# remote_emergency_switch.net
KiCad netlist of a schematic drawn in EAGLE
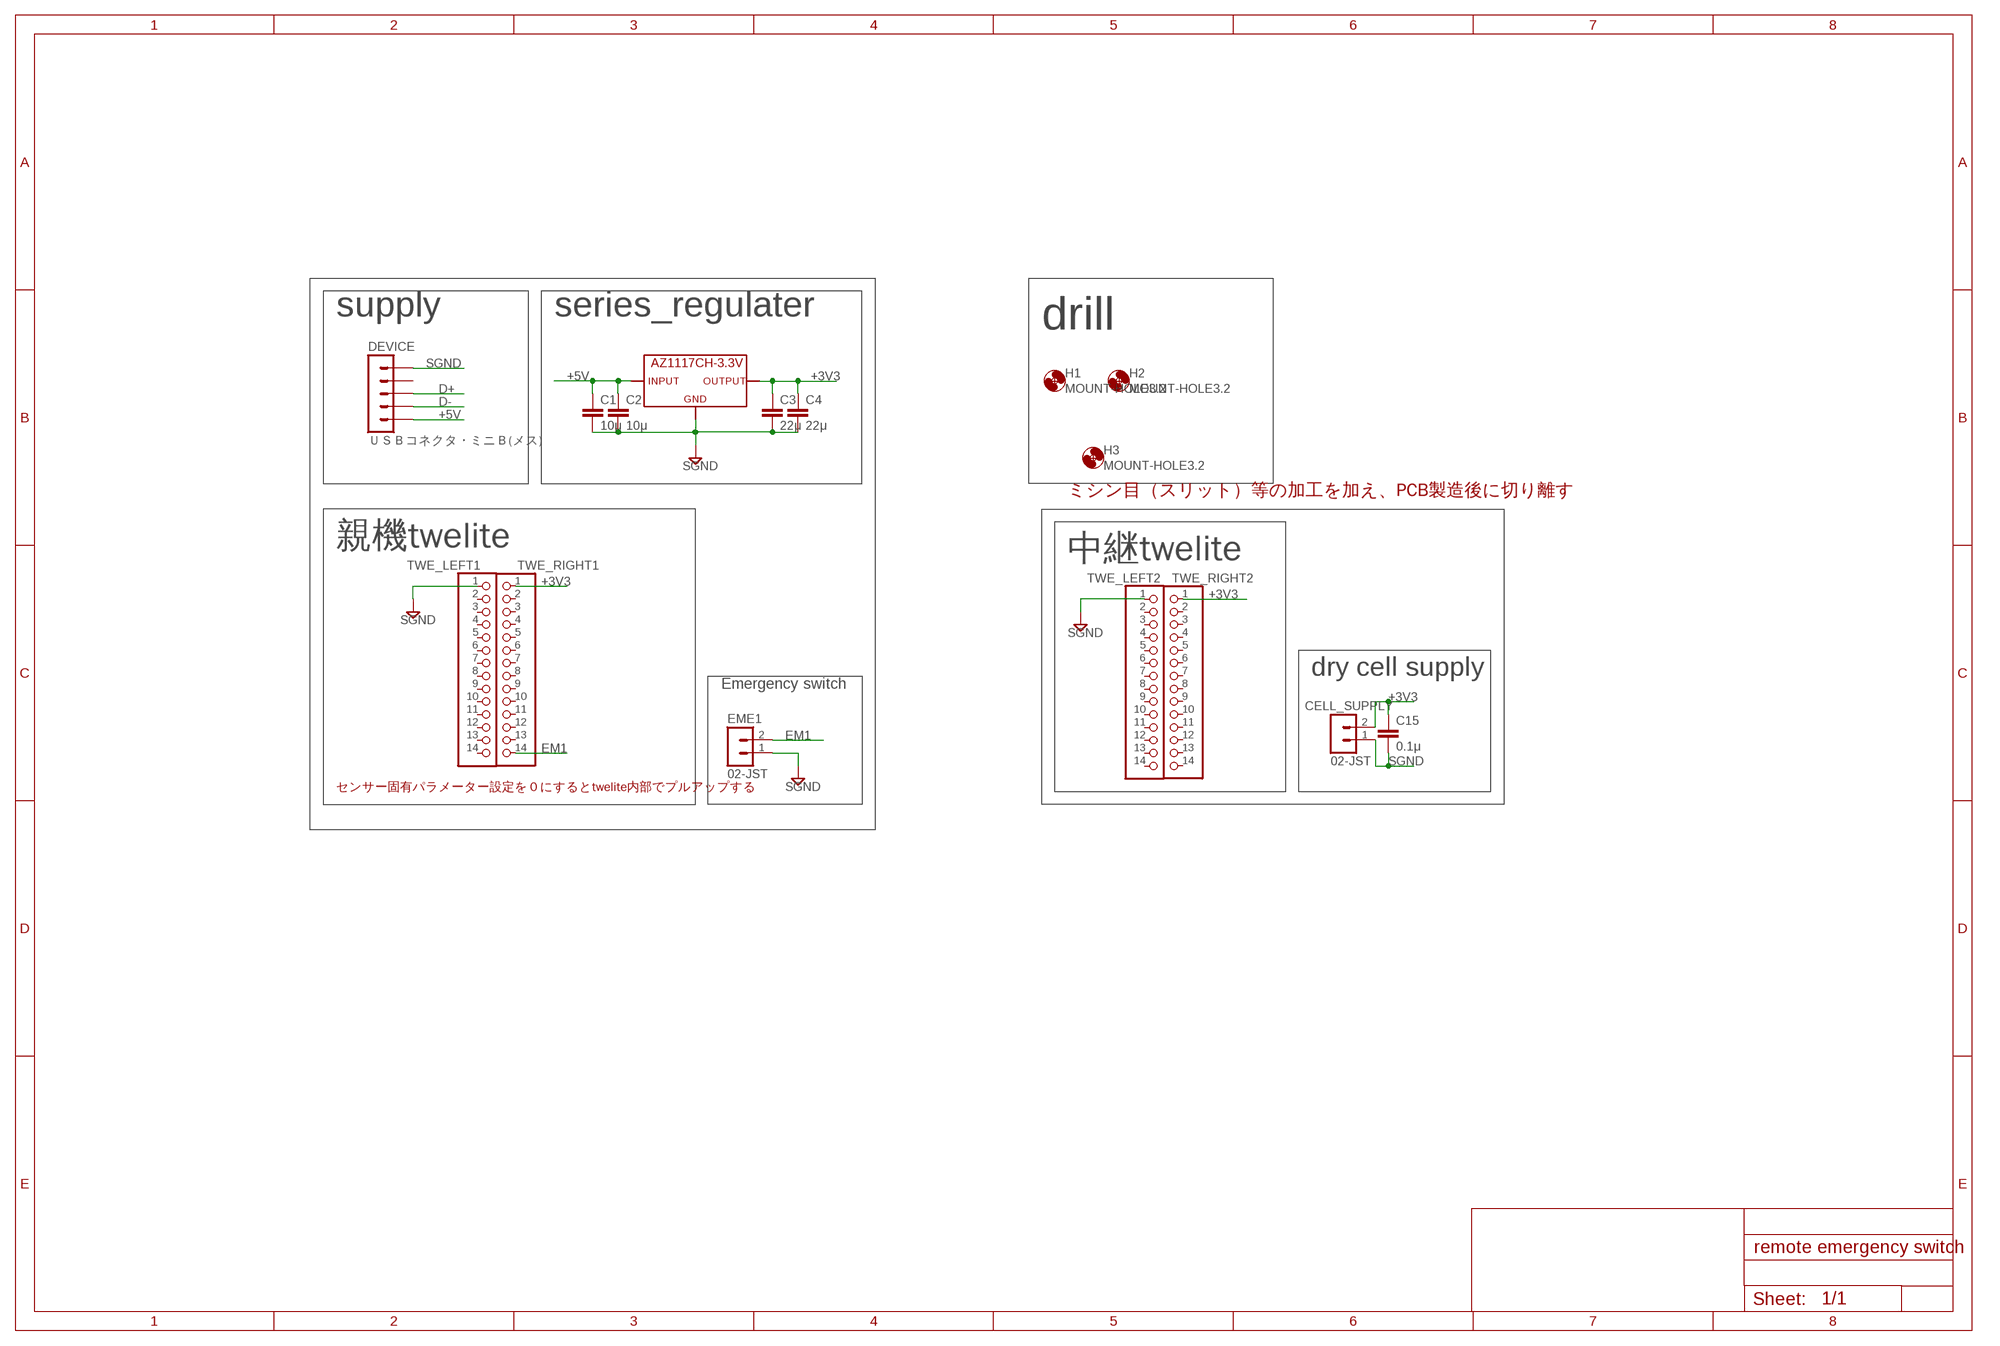
[diagram p0: schematic, sheet 1]

(export (version "E")
  (design (tool "Eeschema 10.0.6"))
  (components
    (comp (ref "C1")
      (value "10μ")
      (footprint "eagle-import:GRM0335C1E240GA01D")
      (libsource (lib "eagle-import") (part "GRM0335C1E240GA01D"))
    )
    (comp (ref "C2")
      (value "10μ")
      (footprint "eagle-import:GRM0335C1E240GA01D")
      (libsource (lib "eagle-import") (part "GRM0335C1E240GA01D"))
    )
    (comp (ref "C3")
      (value "22μ")
      (footprint "eagle-import:GRM0335C1E240GA01D")
      (libsource (lib "eagle-import") (part "GRM0335C1E240GA01D"))
    )
    (comp (ref "C4")
      (value "22μ")
      (footprint "eagle-import:GRM0335C1E240GA01D")
      (libsource (lib "eagle-import") (part "GRM0335C1E240GA01D"))
    )
    (comp (ref "C15")
      (value "0.1μ")
      (footprint "eagle-import:C025-024X044")
      (libsource (lib "eagle-import") (part "C-EU025-024X044"))
    )
    (comp (ref "CELL_SUPPLY")
      (value "02-JST")
      (footprint "eagle-import:B2B-XH")
      (libsource (lib "eagle-import") (part "02-JST"))
    )
    (comp (ref "DEVICE")
      (value "ＵＳＢコネクタ・ミニＢ(メス)")
      (footprint "eagle-import:ＵＳＢコネクタ・ミニＢ(メス)")
      (libsource (lib "eagle-import") (part "ＵＳＢコネクタ・ミニＢ(メス)"))
    )
    (comp (ref "EME1")
      (value "02-JST")
      (footprint "eagle-import:B2B-XH")
      (libsource (lib "eagle-import") (part "02-JST"))
    )
    (comp (ref "H1")
      (value "MOUNT-HOLE3.2")
      (footprint "eagle-import:3,2")
      (libsource (lib "eagle-import") (part "MOUNT-HOLE3.2"))
    )
    (comp (ref "H2")
      (value "MOUNT-HOLE3.2")
      (footprint "eagle-import:3,2")
      (libsource (lib "eagle-import") (part "MOUNT-HOLE3.2"))
    )
    (comp (ref "H3")
      (value "MOUNT-HOLE3.2")
      (footprint "eagle-import:3,2")
      (libsource (lib "eagle-import") (part "MOUNT-HOLE3.2"))
    )
    (comp (ref "REGYURETA")
      (value "３．３V")
      (footprint "eagle-import:ＡＺ１１１７ＣＨ－３．３ＴＲＧ１")
      (libsource (lib "eagle-import") (part "ＡＺ１１１７ＣＨ－３．３ＴＲＧ１"))
    )
    (comp (ref "TWE_LEFT1")
      (value "PINHD-1X14")
      (footprint "eagle-import:1X14")
      (libsource (lib "eagle-import") (part "PINHD-1X14"))
    )
    (comp (ref "TWE_LEFT2")
      (value "PINHD-1X14")
      (footprint "eagle-import:1X14")
      (libsource (lib "eagle-import") (part "PINHD-1X14"))
    )
    (comp (ref "TWE_RIGHT1")
      (value "PINHD-1X14")
      (footprint "eagle-import:1X14")
      (libsource (lib "eagle-import") (part "PINHD-1X14"))
    )
    (comp (ref "TWE_RIGHT2")
      (value "PINHD-1X14")
      (footprint "eagle-import:1X14")
      (libsource (lib "eagle-import") (part "PINHD-1X14"))
    )
  )
  (nets
    (net (code "1") (name "/+3V3") (class "Default")
      (node (ref "C15") (pin "1") (pinfunction "1_1") (pintype "passive"))
      (node (ref "C3") (pin "1") (pinfunction "1_1") (pintype "passive"))
      (node (ref "C4") (pin "1") (pinfunction "1_1") (pintype "passive"))
      (node (ref "CELL_SUPPLY") (pin "2") (pinfunction "2_2") (pintype "passive"))
      (node (ref "REGYURETA") (pin "OUTPUT") (pinfunction "OUTPUT_OUTPUT") (pintype "bidirectional"))
      (node (ref "REGYURETA") (pin "VOUT") (pinfunction "OUTPUT_VOUT") (pintype "bidirectional"))
      (node (ref "TWE_RIGHT1") (pin "1") (pinfunction "1_1") (pintype "passive"))
      (node (ref "TWE_RIGHT2") (pin "1") (pinfunction "1_1") (pintype "passive"))
    )
    (net (code "2") (name "/+5V") (class "Default")
      (node (ref "C1") (pin "1") (pinfunction "1_1") (pintype "passive"))
      (node (ref "C2") (pin "1") (pinfunction "1_1") (pintype "passive"))
      (node (ref "DEVICE") (pin "VBUS") (pinfunction "1_VBUS") (pintype "passive"))
      (node (ref "REGYURETA") (pin "INPUT") (pinfunction "INPUT_INPUT") (pintype "bidirectional"))
    )
    (net (code "3") (name "/D+") (class "Default")
      (node (ref "DEVICE") (pin "D+") (pinfunction "3_D+") (pintype "passive"))
    )
    (net (code "4") (name "/D-") (class "Default")
      (node (ref "DEVICE") (pin "D-") (pinfunction "2_D-") (pintype "passive"))
    )
    (net (code "5") (name "/EM1") (class "Default")
      (node (ref "EME1") (pin "2") (pinfunction "2_2") (pintype "passive"))
      (node (ref "TWE_RIGHT1") (pin "14") (pinfunction "14_14") (pintype "passive"))
    )
    (net (code "6") (name "GND") (class "Default")
      (node (ref "C1") (pin "2") (pinfunction "2_2") (pintype "passive"))
      (node (ref "C15") (pin "2") (pinfunction "2_2") (pintype "passive"))
      (node (ref "C2") (pin "2") (pinfunction "2_2") (pintype "passive"))
      (node (ref "C3") (pin "2") (pinfunction "2_2") (pintype "passive"))
      (node (ref "C4") (pin "2") (pinfunction "2_2") (pintype "passive"))
      (node (ref "CELL_SUPPLY") (pin "1") (pinfunction "1_1") (pintype "passive"))
      (node (ref "DEVICE") (pin "GND") (pinfunction "5_GND") (pintype "passive"))
      (node (ref "EME1") (pin "1") (pinfunction "1_1") (pintype "passive"))
      (node (ref "REGYURETA") (pin "ADJ/GND") (pinfunction "GND_ADJ/GND") (pintype "bidirectional"))
      (node (ref "TWE_LEFT1") (pin "1") (pinfunction "1_1") (pintype "passive"))
      (node (ref "TWE_LEFT2") (pin "1") (pinfunction "1_1") (pintype "passive"))
    )
    (net (code "7") (name "unconnected-(DEVICE-4-PadID)") (class "Default")
      (node (ref "DEVICE") (pin "ID") (pinfunction "4_ID") (pintype "passive"))
    )
    (net (code "8") (name "unconnected-(TWE_LEFT1-Pad2)") (class "Default")
      (node (ref "TWE_LEFT1") (pin "2") (pinfunction "2_2") (pintype "passive"))
    )
    (net (code "9") (name "unconnected-(TWE_LEFT1-Pad3)") (class "Default")
      (node (ref "TWE_LEFT1") (pin "3") (pinfunction "3_3") (pintype "passive"))
    )
    (net (code "10") (name "unconnected-(TWE_LEFT1-Pad4)") (class "Default")
      (node (ref "TWE_LEFT1") (pin "4") (pinfunction "4_4") (pintype "passive"))
    )
    (net (code "11") (name "unconnected-(TWE_LEFT1-Pad5)") (class "Default")
      (node (ref "TWE_LEFT1") (pin "5") (pinfunction "5_5") (pintype "passive"))
    )
    (net (code "12") (name "unconnected-(TWE_LEFT1-Pad6)") (class "Default")
      (node (ref "TWE_LEFT1") (pin "6") (pinfunction "6_6") (pintype "passive"))
    )
    (net (code "13") (name "unconnected-(TWE_LEFT1-Pad7)") (class "Default")
      (node (ref "TWE_LEFT1") (pin "7") (pinfunction "7_7") (pintype "passive"))
    )
    (net (code "14") (name "unconnected-(TWE_LEFT1-Pad8)") (class "Default")
      (node (ref "TWE_LEFT1") (pin "8") (pinfunction "8_8") (pintype "passive"))
    )
    (net (code "15") (name "unconnected-(TWE_LEFT1-Pad9)") (class "Default")
      (node (ref "TWE_LEFT1") (pin "9") (pinfunction "9_9") (pintype "passive"))
    )
    (net (code "16") (name "unconnected-(TWE_LEFT1-Pad10)") (class "Default")
      (node (ref "TWE_LEFT1") (pin "10") (pinfunction "10_10") (pintype "passive"))
    )
    (net (code "17") (name "unconnected-(TWE_LEFT1-Pad11)") (class "Default")
      (node (ref "TWE_LEFT1") (pin "11") (pinfunction "11_11") (pintype "passive"))
    )
    (net (code "18") (name "unconnected-(TWE_LEFT1-Pad12)") (class "Default")
      (node (ref "TWE_LEFT1") (pin "12") (pinfunction "12_12") (pintype "passive"))
    )
    (net (code "19") (name "unconnected-(TWE_LEFT1-Pad13)") (class "Default")
      (node (ref "TWE_LEFT1") (pin "13") (pinfunction "13_13") (pintype "passive"))
    )
    (net (code "20") (name "unconnected-(TWE_LEFT1-Pad14)") (class "Default")
      (node (ref "TWE_LEFT1") (pin "14") (pinfunction "14_14") (pintype "passive"))
    )
    (net (code "21") (name "unconnected-(TWE_LEFT2-Pad2)") (class "Default")
      (node (ref "TWE_LEFT2") (pin "2") (pinfunction "2_2") (pintype "passive"))
    )
    (net (code "22") (name "unconnected-(TWE_LEFT2-Pad3)") (class "Default")
      (node (ref "TWE_LEFT2") (pin "3") (pinfunction "3_3") (pintype "passive"))
    )
    (net (code "23") (name "unconnected-(TWE_LEFT2-Pad4)") (class "Default")
      (node (ref "TWE_LEFT2") (pin "4") (pinfunction "4_4") (pintype "passive"))
    )
    (net (code "24") (name "unconnected-(TWE_LEFT2-Pad5)") (class "Default")
      (node (ref "TWE_LEFT2") (pin "5") (pinfunction "5_5") (pintype "passive"))
    )
    (net (code "25") (name "unconnected-(TWE_LEFT2-Pad6)") (class "Default")
      (node (ref "TWE_LEFT2") (pin "6") (pinfunction "6_6") (pintype "passive"))
    )
    (net (code "26") (name "unconnected-(TWE_LEFT2-Pad7)") (class "Default")
      (node (ref "TWE_LEFT2") (pin "7") (pinfunction "7_7") (pintype "passive"))
    )
    (net (code "27") (name "unconnected-(TWE_LEFT2-Pad8)") (class "Default")
      (node (ref "TWE_LEFT2") (pin "8") (pinfunction "8_8") (pintype "passive"))
    )
    (net (code "28") (name "unconnected-(TWE_LEFT2-Pad9)") (class "Default")
      (node (ref "TWE_LEFT2") (pin "9") (pinfunction "9_9") (pintype "passive"))
    )
    (net (code "29") (name "unconnected-(TWE_LEFT2-Pad10)") (class "Default")
      (node (ref "TWE_LEFT2") (pin "10") (pinfunction "10_10") (pintype "passive"))
    )
    (net (code "30") (name "unconnected-(TWE_LEFT2-Pad11)") (class "Default")
      (node (ref "TWE_LEFT2") (pin "11") (pinfunction "11_11") (pintype "passive"))
    )
    (net (code "31") (name "unconnected-(TWE_LEFT2-Pad12)") (class "Default")
      (node (ref "TWE_LEFT2") (pin "12") (pinfunction "12_12") (pintype "passive"))
    )
    (net (code "32") (name "unconnected-(TWE_LEFT2-Pad13)") (class "Default")
      (node (ref "TWE_LEFT2") (pin "13") (pinfunction "13_13") (pintype "passive"))
    )
    (net (code "33") (name "unconnected-(TWE_LEFT2-Pad14)") (class "Default")
      (node (ref "TWE_LEFT2") (pin "14") (pinfunction "14_14") (pintype "passive"))
    )
    (net (code "34") (name "unconnected-(TWE_RIGHT1-Pad2)") (class "Default")
      (node (ref "TWE_RIGHT1") (pin "2") (pinfunction "2_2") (pintype "passive"))
    )
    (net (code "35") (name "unconnected-(TWE_RIGHT1-Pad3)") (class "Default")
      (node (ref "TWE_RIGHT1") (pin "3") (pinfunction "3_3") (pintype "passive"))
    )
    (net (code "36") (name "unconnected-(TWE_RIGHT1-Pad4)") (class "Default")
      (node (ref "TWE_RIGHT1") (pin "4") (pinfunction "4_4") (pintype "passive"))
    )
    (net (code "37") (name "unconnected-(TWE_RIGHT1-Pad5)") (class "Default")
      (node (ref "TWE_RIGHT1") (pin "5") (pinfunction "5_5") (pintype "passive"))
    )
    (net (code "38") (name "unconnected-(TWE_RIGHT1-Pad6)") (class "Default")
      (node (ref "TWE_RIGHT1") (pin "6") (pinfunction "6_6") (pintype "passive"))
    )
    (net (code "39") (name "unconnected-(TWE_RIGHT1-Pad7)") (class "Default")
      (node (ref "TWE_RIGHT1") (pin "7") (pinfunction "7_7") (pintype "passive"))
    )
    (net (code "40") (name "unconnected-(TWE_RIGHT1-Pad8)") (class "Default")
      (node (ref "TWE_RIGHT1") (pin "8") (pinfunction "8_8") (pintype "passive"))
    )
    (net (code "41") (name "unconnected-(TWE_RIGHT1-Pad9)") (class "Default")
      (node (ref "TWE_RIGHT1") (pin "9") (pinfunction "9_9") (pintype "passive"))
    )
    (net (code "42") (name "unconnected-(TWE_RIGHT1-Pad10)") (class "Default")
      (node (ref "TWE_RIGHT1") (pin "10") (pinfunction "10_10") (pintype "passive"))
    )
    (net (code "43") (name "unconnected-(TWE_RIGHT1-Pad11)") (class "Default")
      (node (ref "TWE_RIGHT1") (pin "11") (pinfunction "11_11") (pintype "passive"))
    )
    (net (code "44") (name "unconnected-(TWE_RIGHT1-Pad12)") (class "Default")
      (node (ref "TWE_RIGHT1") (pin "12") (pinfunction "12_12") (pintype "passive"))
    )
    (net (code "45") (name "unconnected-(TWE_RIGHT1-Pad13)") (class "Default")
      (node (ref "TWE_RIGHT1") (pin "13") (pinfunction "13_13") (pintype "passive"))
    )
    (net (code "46") (name "unconnected-(TWE_RIGHT2-Pad2)") (class "Default")
      (node (ref "TWE_RIGHT2") (pin "2") (pinfunction "2_2") (pintype "passive"))
    )
    (net (code "47") (name "unconnected-(TWE_RIGHT2-Pad3)") (class "Default")
      (node (ref "TWE_RIGHT2") (pin "3") (pinfunction "3_3") (pintype "passive"))
    )
    (net (code "48") (name "unconnected-(TWE_RIGHT2-Pad4)") (class "Default")
      (node (ref "TWE_RIGHT2") (pin "4") (pinfunction "4_4") (pintype "passive"))
    )
    (net (code "49") (name "unconnected-(TWE_RIGHT2-Pad5)") (class "Default")
      (node (ref "TWE_RIGHT2") (pin "5") (pinfunction "5_5") (pintype "passive"))
    )
    (net (code "50") (name "unconnected-(TWE_RIGHT2-Pad6)") (class "Default")
      (node (ref "TWE_RIGHT2") (pin "6") (pinfunction "6_6") (pintype "passive"))
    )
    (net (code "51") (name "unconnected-(TWE_RIGHT2-Pad7)") (class "Default")
      (node (ref "TWE_RIGHT2") (pin "7") (pinfunction "7_7") (pintype "passive"))
    )
    (net (code "52") (name "unconnected-(TWE_RIGHT2-Pad8)") (class "Default")
      (node (ref "TWE_RIGHT2") (pin "8") (pinfunction "8_8") (pintype "passive"))
    )
    (net (code "53") (name "unconnected-(TWE_RIGHT2-Pad9)") (class "Default")
      (node (ref "TWE_RIGHT2") (pin "9") (pinfunction "9_9") (pintype "passive"))
    )
    (net (code "54") (name "unconnected-(TWE_RIGHT2-Pad10)") (class "Default")
      (node (ref "TWE_RIGHT2") (pin "10") (pinfunction "10_10") (pintype "passive"))
    )
    (net (code "55") (name "unconnected-(TWE_RIGHT2-Pad11)") (class "Default")
      (node (ref "TWE_RIGHT2") (pin "11") (pinfunction "11_11") (pintype "passive"))
    )
    (net (code "56") (name "unconnected-(TWE_RIGHT2-Pad12)") (class "Default")
      (node (ref "TWE_RIGHT2") (pin "12") (pinfunction "12_12") (pintype "passive"))
    )
    (net (code "57") (name "unconnected-(TWE_RIGHT2-Pad13)") (class "Default")
      (node (ref "TWE_RIGHT2") (pin "13") (pinfunction "13_13") (pintype "passive"))
    )
    (net (code "58") (name "unconnected-(TWE_RIGHT2-Pad14)") (class "Default")
      (node (ref "TWE_RIGHT2") (pin "14") (pinfunction "14_14") (pintype "passive"))
    )
  )
)
